# Sheet2.net
KiCad netlist of a schematic drawn in Altium Designer
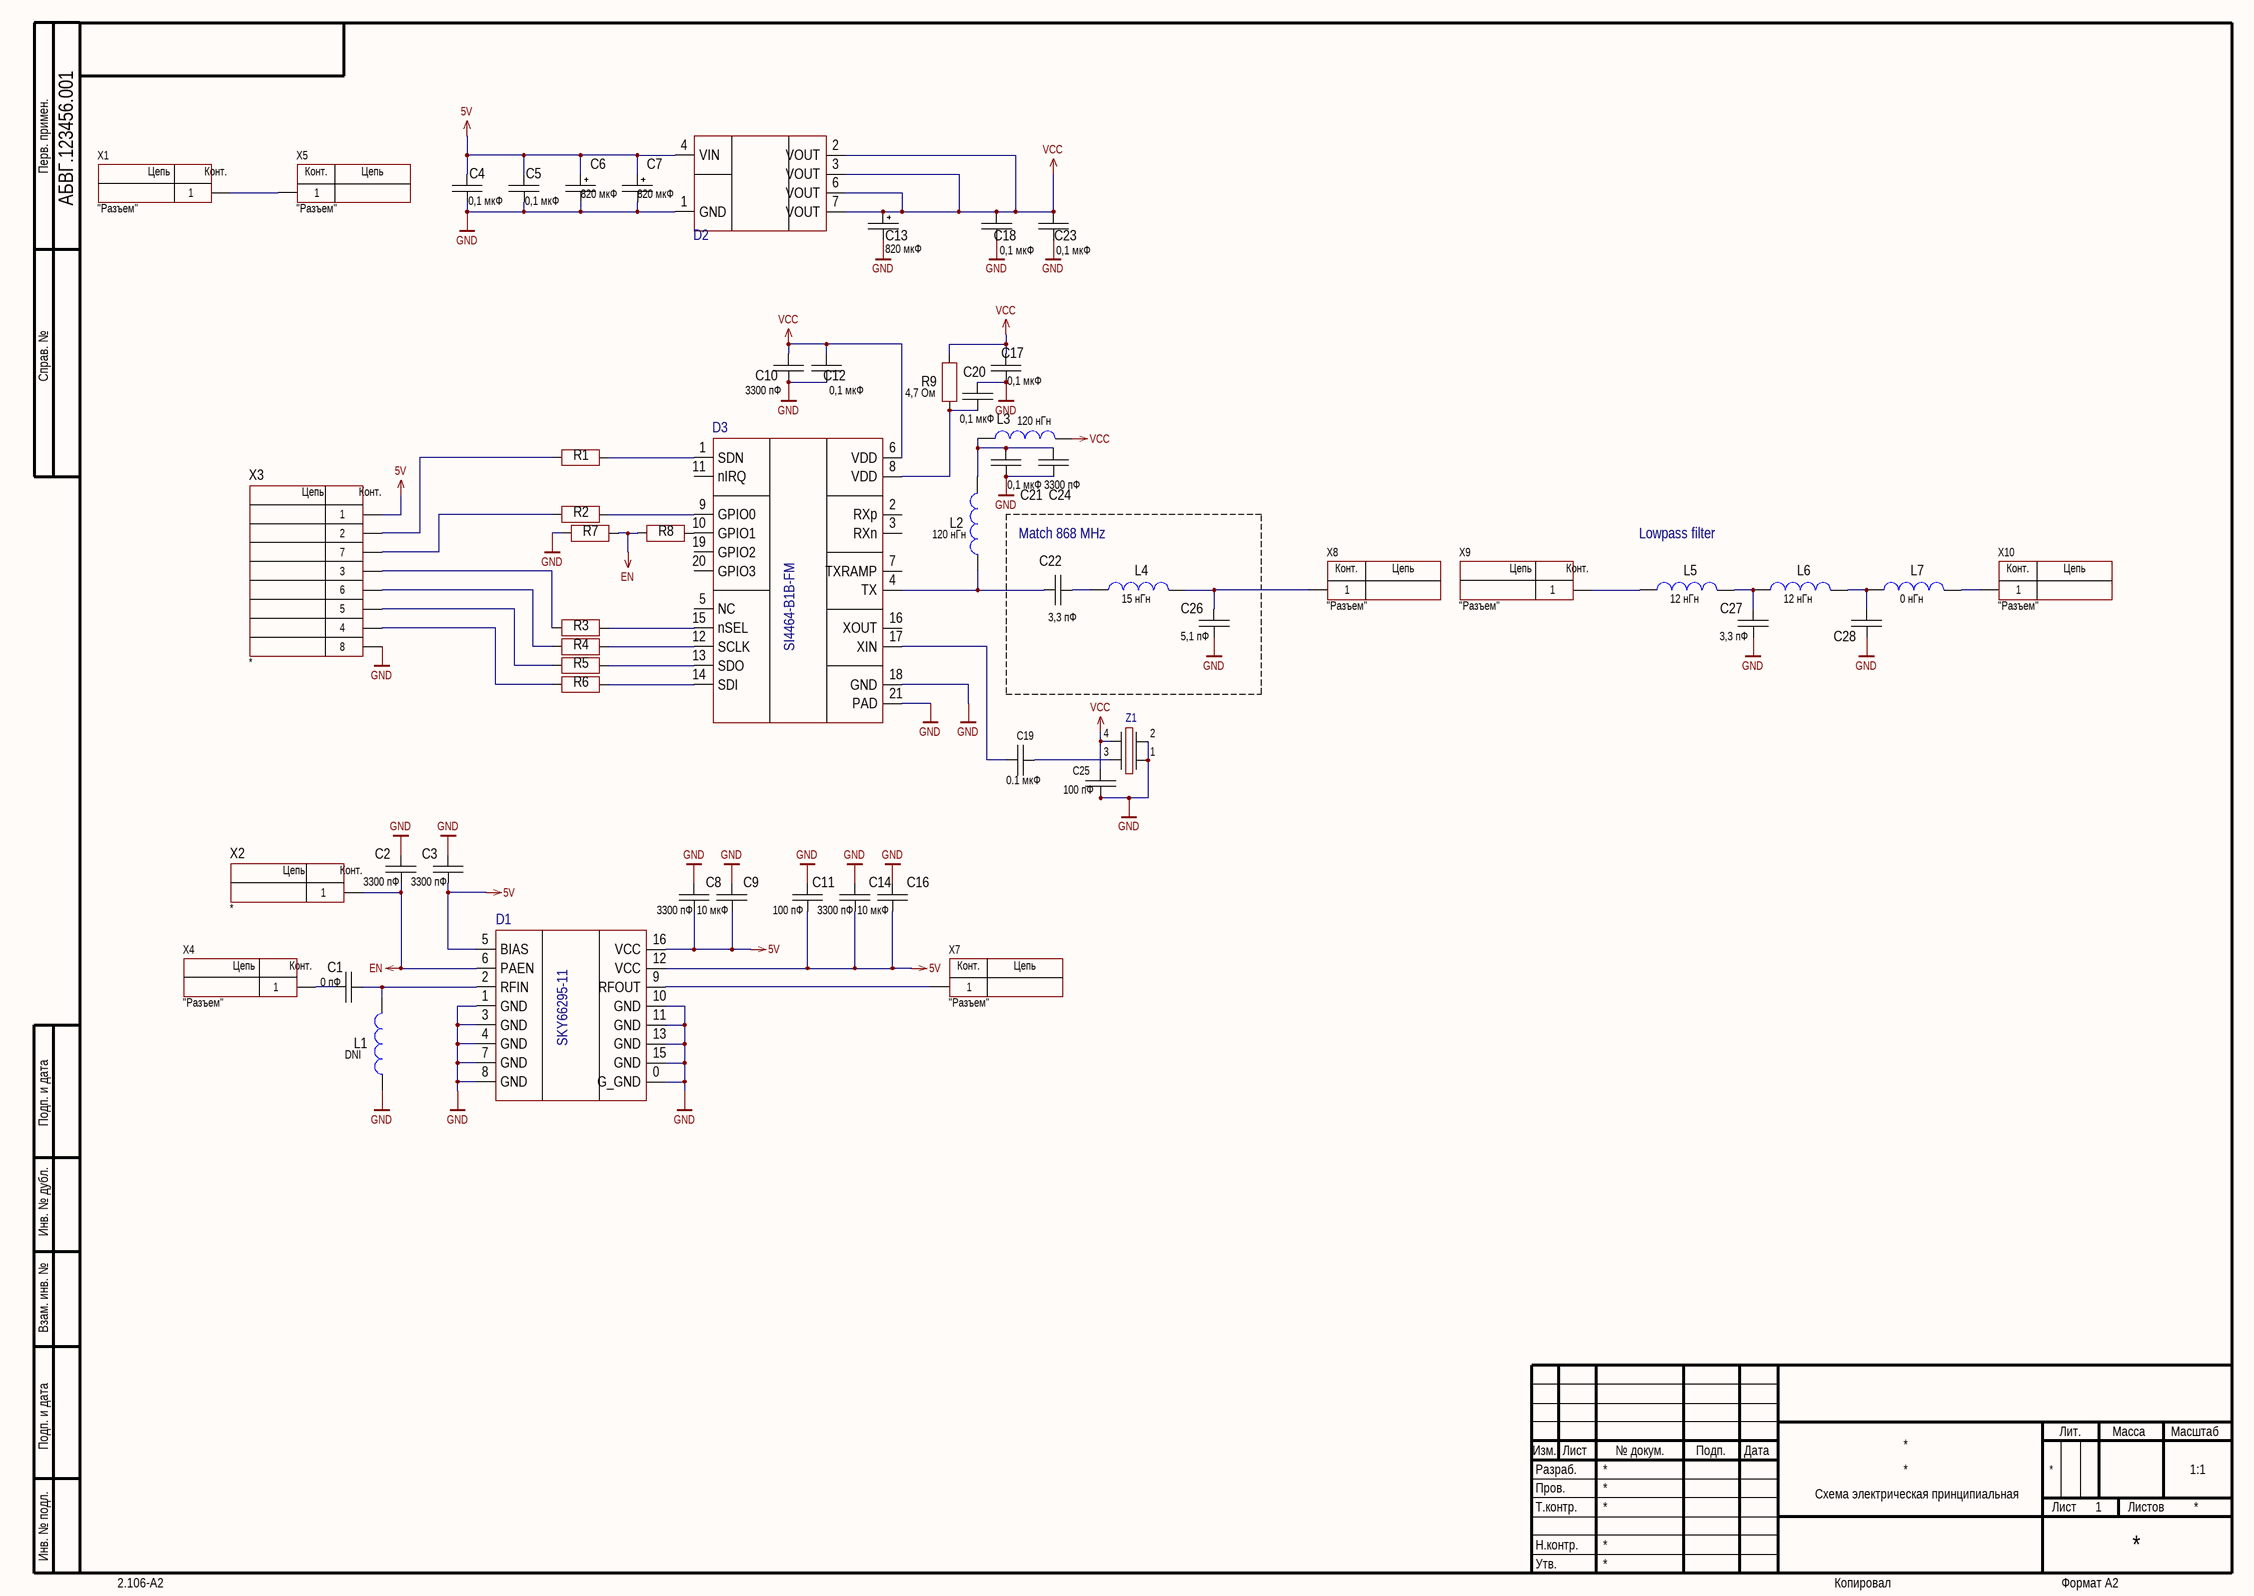
[diagram p0: Sheet2.SchDoc]

(export (version "E")
  (design (tool "Eeschema 10.0.6"))
  (components
    (comp (ref "C1")
      (value "0 пФ")
      (footprint "CH0603C")
      (fields
        (field (name "MANUFACTURER") "MURATA")
        (field (name "TOLERANCE") "±5%")
        (field (name "VALUEMANUFACTURERPARTNUMBER") "0603-NP0-50В-0 пФ±5% MURATA")
      )
      (libsource (lib "Discrete") (part "Capacitor"))
    )
    (comp (ref "C2")
      (value "3300 пФ")
      (footprint "CH0603C")
      (fields
        (field (name "MANUFACTURER") "MURATA")
        (field (name "TOLERANCE") "±5%")
        (field (name "VALUEMANUFACTURERPARTNUMBER") "0603-NP0-50В-3300 пФ±5% MURATA")
      )
      (libsource (lib "Discrete") (part "Capacitor"))
    )
    (comp (ref "C3")
      (value "3300 пФ")
      (footprint "CH0603C")
      (fields
        (field (name "MANUFACTURER") "MURATA")
        (field (name "TOLERANCE") "±5%")
        (field (name "VALUEMANUFACTURERPARTNUMBER") "0603-NP0-50В-3300 пФ±5% MURATA")
      )
      (libsource (lib "Discrete") (part "Capacitor"))
    )
    (comp (ref "C4")
      (value "0,1 мкФ")
      (footprint "CH0603C")
      (fields
        (field (name "MANUFACTURER") "MURATA")
        (field (name "TOLERANCE") "±5%")
        (field (name "VALUEMANUFACTURERPARTNUMBER") "0603-X7R-50В-0,1 мкФ±5% MURATA")
      )
      (libsource (lib "Discrete") (part "Capacitor"))
    )
    (comp (ref "C5")
      (value "0,1 мкФ")
      (footprint "CH0603C")
      (fields
        (field (name "MANUFACTURER") "MURATA")
        (field (name "TOLERANCE") "±5%")
        (field (name "VALUEMANUFACTURERPARTNUMBER") "0603-X7R-50В-0,1 мкФ±5% MURATA")
      )
      (libsource (lib "Discrete") (part "Capacitor"))
    )
    (comp (ref "C6")
      (value "820 мкФ")
      (footprint "D8C3.5H12")
      (fields (field (name "MANUFACTURER") "KEMET"))
      (libsource (lib "Discrete") (part "AlumCap"))
    )
    (comp (ref "C7")
      (value "820 мкФ")
      (footprint "D8C3.5H12")
      (fields (field (name "MANUFACTURER") "KEMET"))
      (libsource (lib "Discrete") (part "AlumCap"))
    )
    (comp (ref "C8")
      (value "3300 пФ")
      (footprint "CH0603C")
      (fields
        (field (name "MANUFACTURER") "MURATA")
        (field (name "TOLERANCE") "±5%")
        (field (name "VALUEMANUFACTURERPARTNUMBER") "0603-NP0-50В-3300 пФ±5% MURATA")
      )
      (libsource (lib "Discrete") (part "Capacitor"))
    )
    (comp (ref "C9")
      (value "10 мкФ")
      (footprint "CH1206C")
      (fields
        (field (name "MANUFACTURER") "MURATA")
        (field (name "TOLERANCE") "±5%")
        (field (name "VALUEMANUFACTURERPARTNUMBER") "1206-X7R-50В-10 мкФ±5% MURATA")
      )
      (libsource (lib "Discrete") (part "Capacitor"))
    )
    (comp (ref "C10")
      (value "3300 пФ")
      (footprint "CH0603C")
      (fields
        (field (name "MANUFACTURER") "MURATA")
        (field (name "TOLERANCE") "±5%")
        (field (name "VALUEMANUFACTURERPARTNUMBER") "0603-NP0-50В-3300 пФ±5% MURATA")
      )
      (libsource (lib "Discrete") (part "Capacitor"))
    )
    (comp (ref "C11")
      (value "100 пФ")
      (footprint "CH0603C")
      (fields
        (field (name "MANUFACTURER") "MURATA")
        (field (name "TOLERANCE") "±5%")
        (field (name "VALUEMANUFACTURERPARTNUMBER") "0603-NP0-50В-100 пФ±5% MURATA")
      )
      (libsource (lib "Discrete") (part "Capacitor"))
    )
    (comp (ref "C12")
      (value "0,1 мкФ")
      (footprint "CH0603C")
      (fields
        (field (name "MANUFACTURER") "MURATA")
        (field (name "TOLERANCE") "±5%")
        (field (name "VALUEMANUFACTURERPARTNUMBER") "0603-X7R-50В-0,1 мкФ±5% MURATA")
      )
      (libsource (lib "Discrete") (part "Capacitor"))
    )
    (comp (ref "C13")
      (value "820 мкФ")
      (footprint "D8C3.5H12")
      (fields (field (name "MANUFACTURER") "KEMET"))
      (libsource (lib "Discrete") (part "AlumCap"))
    )
    (comp (ref "C14")
      (value "3300 пФ")
      (footprint "CH0603C")
      (fields
        (field (name "MANUFACTURER") "MURATA")
        (field (name "TOLERANCE") "±5%")
        (field (name "VALUEMANUFACTURERPARTNUMBER") "0603-NP0-50В-3300 пФ±5% MURATA")
      )
      (libsource (lib "Discrete") (part "Capacitor"))
    )
    (comp (ref "C16")
      (value "10 мкФ")
      (footprint "CH1206C")
      (fields
        (field (name "MANUFACTURER") "MURATA")
        (field (name "TOLERANCE") "±5%")
        (field (name "VALUEMANUFACTURERPARTNUMBER") "1206-X7R-50В-10 мкФ±5% MURATA")
      )
      (libsource (lib "Discrete") (part "Capacitor"))
    )
    (comp (ref "C17")
      (value "0,1 мкФ")
      (footprint "CH0603C")
      (fields
        (field (name "MANUFACTURER") "MURATA")
        (field (name "TOLERANCE") "±5%")
        (field (name "VALUEMANUFACTURERPARTNUMBER") "0603-X7R-50В-0,1 мкФ±5% MURATA")
      )
      (libsource (lib "Discrete") (part "Capacitor"))
    )
    (comp (ref "C18")
      (value "0,1 мкФ")
      (footprint "CH0603C")
      (fields
        (field (name "MANUFACTURER") "MURATA")
        (field (name "TOLERANCE") "±5%")
        (field (name "VALUEMANUFACTURERPARTNUMBER") "0603-X7R-50В-0,1 мкФ±5% MURATA")
      )
      (libsource (lib "Discrete") (part "Capacitor"))
    )
    (comp (ref "C19")
      (value "0.1 мкФ")
      (footprint "CAP: 0603")
      (fields
        (field (name "MANUFACTURER") "Yageo")
        (field (name "PARTNUMBER") "CC0603KRX7R7BB104")
        (field (name "VALUEMANUFACTURERPARTNUMBER") "Ceramic capacitor, 0.1 мкФ, X7R, ±10%, 16V, 0603, -55...+125°C")
      )
      (libsource (lib "Capacitor") (part "Ceramic_0603"))
    )
    (comp (ref "C20")
      (value "0,1 мкФ")
      (footprint "CH0603C")
      (fields
        (field (name "MANUFACTURER") "MURATA")
        (field (name "TOLERANCE") "±5%")
        (field (name "VALUEMANUFACTURERPARTNUMBER") "0603-X7R-50В-0,1 мкФ±5% MURATA")
      )
      (libsource (lib "Discrete") (part "Capacitor"))
    )
    (comp (ref "C21")
      (value "0,1 мкФ")
      (footprint "CH0603C")
      (fields
        (field (name "MANUFACTURER") "MURATA")
        (field (name "TOLERANCE") "±5%")
        (field (name "VALUEMANUFACTURERPARTNUMBER") "0603-X7R-50В-0,1 мкФ±5% MURATA")
      )
      (libsource (lib "Discrete") (part "Capacitor"))
    )
    (comp (ref "C22")
      (value "3,3 пФ")
      (footprint "CH0603C")
      (fields
        (field (name "MANUFACTURER") "MURATA")
        (field (name "TOLERANCE") "±5%")
        (field (name "VALUEMANUFACTURERPARTNUMBER") "0603-NP0-50В-3,3 пФ±5% MURATA")
      )
      (libsource (lib "Discrete") (part "Capacitor"))
    )
    (comp (ref "C23")
      (value "0,1 мкФ")
      (footprint "CH0603C")
      (fields
        (field (name "MANUFACTURER") "MURATA")
        (field (name "TOLERANCE") "±5%")
        (field (name "VALUEMANUFACTURERPARTNUMBER") "0603-X7R-50В-0,1 мкФ±5% MURATA")
      )
      (libsource (lib "Discrete") (part "Capacitor"))
    )
    (comp (ref "C24")
      (value "3300 пФ")
      (footprint "CH0603C")
      (fields
        (field (name "MANUFACTURER") "MURATA")
        (field (name "TOLERANCE") "±5%")
        (field (name "VALUEMANUFACTURERPARTNUMBER") "0603-NP0-50В-3300 пФ±5% MURATA")
      )
      (libsource (lib "Discrete") (part "Capacitor"))
    )
    (comp (ref "C25")
      (value "100 пФ")
      (footprint "CAP: 0603")
      (fields
        (field (name "MANUFACTURER") "Yageo")
        (field (name "PARTNUMBER") "CC0603KRX7R7BB104")
        (field (name "VALUEMANUFACTURERPARTNUMBER") "Ceramic capacitor, 100 пФ, NP0, ±10%, 16V, 0603, -55...+125°C")
      )
      (libsource (lib "Capacitor") (part "Ceramic_0603"))
    )
    (comp (ref "C26")
      (value "5,1 пФ")
      (footprint "CH0603C")
      (fields
        (field (name "MANUFACTURER") "MURATA")
        (field (name "TOLERANCE") "±5%")
        (field (name "VALUEMANUFACTURERPARTNUMBER") "0603-NP0-50В-5,1 пФ±5% MURATA")
      )
      (libsource (lib "Discrete") (part "Capacitor"))
    )
    (comp (ref "C27")
      (value "3,3 пФ")
      (footprint "CH0603C")
      (fields
        (field (name "MANUFACTURER") "MURATA")
        (field (name "TOLERANCE") "±5%")
        (field (name "VALUEMANUFACTURERPARTNUMBER") "0603-NP0-50В-3,3 пФ±5% MURATA")
      )
      (libsource (lib "Discrete") (part "Capacitor"))
    )
    (comp (ref "C28")
      (value "10 пФ")
      (footprint "CH0603C")
      (fields
        (field (name "MANUFACTURER") "MURATA")
        (field (name "TOLERANCE") "±5%")
        (field (name "VALUEMANUFACTURERPARTNUMBER") "0603-NP0-50В-10 пФ±5% MURATA")
      )
      (libsource (lib "Discrete") (part "Capacitor"))
    )
    (comp (ref "D1")
      (value "SKY66295-11")
      (footprint "16-LGA (5x5)")
      (description "800 to 900 MHz High-Efficiency 4 W Power Amplifier")
      (fields (field (name "VALUEMANUFACTURERPARTNUMBER") "SKY66295-11 *"))
      (libsource (lib "Analog") (part "SKY66295-11"))
    )
    (comp (ref "D2")
      (value "LD1117D33")
      (footprint "8-SOIC")
      (fields (field (name "MANUFACTURER") "ST MICROELECTRONICS"))
      (libsource (lib "Power Supplies") (part "LD1117D33"))
    )
    (comp (ref "D3")
      (value "SI4464-B1B-FM")
      (footprint "20-QFN (4x4)")
      (description "RF Transceiver FSK/GFSK/GMSK/MSK/OOK 3.3V 20-Pin QFN")
      (fields
        (field (name "MANUFACTURER") "SILICON LABS")
        (field (name "VALUEMANUFACTURERPARTNUMBER") "SI4464-B1B-FM SILICON LABS")
      )
      (libsource (lib "Digital") (part "SI4464"))
    )
    (comp (ref "L1")
      (value "DNI")
      (footprint "CH0603L")
      (fields (field (name "TOLERANCE") "±5%") (field (name "VALUEMANUFACTURERPARTNUMBER") "* DNI ±5% *"))
      (libsource (lib "Discrete") (part "Inductor"))
    )
    (comp (ref "L2")
      (value "120 нГн")
      (footprint "CH0603L")
      (fields (field (name "TOLERANCE") "±5%") (field (name "VALUEMANUFACTURERPARTNUMBER") "* 120 нГн ±5% *"))
      (libsource (lib "Discrete") (part "Inductor"))
    )
    (comp (ref "L3")
      (value "120 нГн")
      (footprint "CH0603L")
      (fields (field (name "TOLERANCE") "±5%") (field (name "VALUEMANUFACTURERPARTNUMBER") "* 120 нГн ±5% *"))
      (libsource (lib "Discrete") (part "Inductor"))
    )
    (comp (ref "L4")
      (value "15 нГн")
      (footprint "CH0603L")
      (fields (field (name "TOLERANCE") "±5%") (field (name "VALUEMANUFACTURERPARTNUMBER") "* 15 нГн ±5% *"))
      (libsource (lib "Discrete") (part "Inductor"))
    )
    (comp (ref "L5")
      (value "12 нГн")
      (footprint "CH0603L")
      (fields (field (name "TOLERANCE") "±5%") (field (name "VALUEMANUFACTURERPARTNUMBER") "* 12 нГн ±5% *"))
      (libsource (lib "Discrete") (part "Inductor"))
    )
    (comp (ref "L6")
      (value "12 нГн")
      (footprint "CH0603L")
      (fields (field (name "TOLERANCE") "±5%") (field (name "VALUEMANUFACTURERPARTNUMBER") "* 12 нГн ±5% *"))
      (libsource (lib "Discrete") (part "Inductor"))
    )
    (comp (ref "L7")
      (value "0 нГн")
      (footprint "CH0603L")
      (fields (field (name "TOLERANCE") "±5%") (field (name "VALUEMANUFACTURERPARTNUMBER") "* 0 нГн ±5% *"))
      (libsource (lib "Discrete") (part "Inductor"))
    )
    (comp (ref "R1")
      (value "100 Ом")
      (footprint "CH0603R")
      (fields
        (field (name "MANUFACTURER") "YAGEO")
        (field (name "TOLERANCE") "± 5%")
        (field (name "VALUEMANUFACTURERPARTNUMBER") "RC0603-0,1-100 Ом ± 5% YAGEO")
      )
      (libsource (lib "Discrete") (part "Resistor"))
    )
    (comp (ref "R2")
      (value "100 Ом")
      (footprint "CH0603R")
      (fields
        (field (name "MANUFACTURER") "YAGEO")
        (field (name "TOLERANCE") "± 5%")
        (field (name "VALUEMANUFACTURERPARTNUMBER") "RC0603-0,1-100 Ом ± 5% YAGEO")
      )
      (libsource (lib "Discrete") (part "Resistor"))
    )
    (comp (ref "R3")
      (value "100 Ом")
      (footprint "CH0603R")
      (fields
        (field (name "MANUFACTURER") "YAGEO")
        (field (name "TOLERANCE") "± 5%")
        (field (name "VALUEMANUFACTURERPARTNUMBER") "RC0603-0,1-100 Ом ± 5% YAGEO")
      )
      (libsource (lib "Discrete") (part "Resistor"))
    )
    (comp (ref "R4")
      (value "100 Ом")
      (footprint "CH0603R")
      (fields
        (field (name "MANUFACTURER") "YAGEO")
        (field (name "TOLERANCE") "± 5%")
        (field (name "VALUEMANUFACTURERPARTNUMBER") "RC0603-0,1-100 Ом ± 5% YAGEO")
      )
      (libsource (lib "Discrete") (part "Resistor"))
    )
    (comp (ref "R5")
      (value "100 Ом")
      (footprint "CH0603R")
      (fields
        (field (name "MANUFACTURER") "YAGEO")
        (field (name "TOLERANCE") "± 5%")
        (field (name "VALUEMANUFACTURERPARTNUMBER") "RC0603-0,1-100 Ом ± 5% YAGEO")
      )
      (libsource (lib "Discrete") (part "Resistor"))
    )
    (comp (ref "R6")
      (value "100 Ом")
      (footprint "CH0603R")
      (fields
        (field (name "MANUFACTURER") "YAGEO")
        (field (name "TOLERANCE") "± 5%")
        (field (name "VALUEMANUFACTURERPARTNUMBER") "RC0603-0,1-100 Ом ± 5% YAGEO")
      )
      (libsource (lib "Discrete") (part "Resistor"))
    )
    (comp (ref "R7")
      (value "1 кОм")
      (footprint "CH0603R")
      (fields
        (field (name "MANUFACTURER") "YAGEO")
        (field (name "TOLERANCE") "± 5%")
        (field (name "VALUEMANUFACTURERPARTNUMBER") "RC0603-0,1-1 кОм ± 5% YAGEO")
      )
      (libsource (lib "Discrete") (part "Resistor"))
    )
    (comp (ref "R8")
      (value "1 кОм")
      (footprint "CH0603R")
      (fields
        (field (name "MANUFACTURER") "YAGEO")
        (field (name "TOLERANCE") "± 5%")
        (field (name "VALUEMANUFACTURERPARTNUMBER") "RC0603-0,1-1 кОм ± 5% YAGEO")
      )
      (libsource (lib "Discrete") (part "Resistor"))
    )
    (comp (ref "R9")
      (value "4,7 Ом")
      (footprint "CH0603R")
      (fields
        (field (name "MANUFACTURER") "YAGEO")
        (field (name "TOLERANCE") "± 5%")
        (field (name "VALUEMANUFACTURERPARTNUMBER") "RC0603-0,1-4,7 Ом ± 5% YAGEO")
      )
      (libsource (lib "") (part "Resistor_1"))
    )
    (comp (ref "X1")
      (value "~")
      (footprint "CON: SMA")
      (fields
        (field (name "MANUFACTURER") "TE Connectivity")
        (field (name "VALUEMANUFACTURERPARTNUMBER") "Connector SMA, 50 Ohm, 3GHz")
        (field (name "PARTNUMBER") "5-1814832-1")
        (field (name "COMMENTTEXT") "\"Разъем\"")
      )
      (libsource (lib "Connector") (part "Connector_SMA"))
    )
    (comp (ref "X2")
      (value "*")
      (footprint "CON: PADS 1x1mm")
      (libsource (lib "Connectors") (part "1-Connector"))
    )
    (comp (ref "X3") (value "*") (footprint "CON: PLS-8") (libsource (lib "Connectors") (part "8-Connector")))
    (comp (ref "X4")
      (value "~")
      (footprint "CON: SMA")
      (fields
        (field (name "MANUFACTURER") "TE Connectivity")
        (field (name "VALUEMANUFACTURERPARTNUMBER") "Connector SMA, 50 Ohm, 3GHz")
        (field (name "PARTNUMBER") "5-1814832-1")
        (field (name "COMMENTTEXT") "\"Разъем\"")
      )
      (libsource (lib "Connector") (part "Connector_SMA"))
    )
    (comp (ref "X5")
      (value "~")
      (footprint "CON: SMA")
      (fields
        (field (name "MANUFACTURER") "TE Connectivity")
        (field (name "VALUEMANUFACTURERPARTNUMBER") "Connector SMA, 50 Ohm, 3GHz")
        (field (name "PARTNUMBER") "5-1814832-1")
        (field (name "COMMENTTEXT") "\"Разъем\"")
      )
      (libsource (lib "") (part "Connector_SMA_1"))
    )
    (comp (ref "X7")
      (value "~")
      (footprint "CON: SMA")
      (fields
        (field (name "MANUFACTURER") "TE Connectivity")
        (field (name "VALUEMANUFACTURERPARTNUMBER") "Connector SMA, 50 Ohm, 3GHz")
        (field (name "PARTNUMBER") "5-1814832-1")
        (field (name "COMMENTTEXT") "\"Разъем\"")
      )
      (libsource (lib "") (part "Connector_SMA_1"))
    )
    (comp (ref "X8")
      (value "~")
      (footprint "CON: SMA")
      (fields
        (field (name "MANUFACTURER") "TE Connectivity")
        (field (name "VALUEMANUFACTURERPARTNUMBER") "Connector SMA, 50 Ohm, 3GHz")
        (field (name "PARTNUMBER") "5-1814832-1")
        (field (name "COMMENTTEXT") "\"Разъем\"")
      )
      (libsource (lib "") (part "Connector_SMA_1"))
    )
    (comp (ref "X9")
      (value "~")
      (footprint "CON: SMA")
      (fields
        (field (name "MANUFACTURER") "TE Connectivity")
        (field (name "VALUEMANUFACTURERPARTNUMBER") "Connector SMA, 50 Ohm, 3GHz")
        (field (name "PARTNUMBER") "5-1814832-1")
        (field (name "COMMENTTEXT") "\"Разъем\"")
      )
      (libsource (lib "Connector") (part "Connector_SMA"))
    )
    (comp (ref "X10")
      (value "~")
      (footprint "CON: SMA")
      (fields
        (field (name "MANUFACTURER") "TE Connectivity")
        (field (name "VALUEMANUFACTURERPARTNUMBER") "Connector SMA, 50 Ohm, 3GHz")
        (field (name "PARTNUMBER") "5-1814832-1")
        (field (name "COMMENTTEXT") "\"Разъем\"")
      )
      (libsource (lib "") (part "Connector_SMA_1"))
    )
    (comp (ref "Z1")
      (value "JT33-B-K-3,3-LF-26,0MHz")
      (footprint "OSC: 3225")
      (fields (field (name "MANUFACTURER") "JAUCH"))
      (libsource (lib "Oscilator") (part "Oscilator_3225"))
    )
  )
  (nets
    (net (code "1") (name "5V") (class "Default")
      (node (ref "C11") (pin "1") (pinfunction "1_1") (pintype "power_in"))
      (node (ref "C14") (pin "1") (pinfunction "1_1") (pintype "power_in"))
      (node (ref "C16") (pin "1") (pinfunction "1_1") (pintype "power_in"))
      (node (ref "C3") (pin "1") (pinfunction "1_1") (pintype "power_in"))
      (node (ref "C4") (pin "2") (pinfunction "2_2") (pintype "power_in"))
      (node (ref "C5") (pin "2") (pinfunction "2_2") (pintype "power_in"))
      (node (ref "C6") (pin "1") (pinfunction "1_1") (pintype "power_in"))
      (node (ref "C7") (pin "1") (pinfunction "1_1") (pintype "power_in"))
      (node (ref "C8") (pin "1") (pinfunction "1_1") (pintype "power_in"))
      (node (ref "C9") (pin "1") (pinfunction "1_1") (pintype "power_in"))
      (node (ref "D1") (pin "12") (pinfunction "VCC_12") (pintype "passive"))
      (node (ref "D1") (pin "16") (pinfunction "VCC_16") (pintype "passive"))
      (node (ref "D1") (pin "5") (pinfunction "BIAS_5") (pintype "passive"))
      (node (ref "D2") (pin "4") (pinfunction "VIN_4") (pintype "power_in"))
      (node (ref "X3") (pin "1") (pinfunction "1_1") (pintype "passive"))
    )
    (net (code "2") (name "EN") (class "Default")
      (node (ref "C2") (pin "1") (pinfunction "1_1") (pintype "power_in"))
      (node (ref "D1") (pin "6") (pinfunction "PAEN_6") (pintype "passive"))
      (node (ref "R7") (pin "1") (pinfunction "1_1") (pintype "passive"))
      (node (ref "R8") (pin "2") (pinfunction "2_2") (pintype "passive"))
      (node (ref "X2") (pin "1") (pinfunction "1_1") (pintype "passive"))
    )
    (net (code "3") (name "GND") (class "Default")
      (node (ref "C10") (pin "1") (pinfunction "1_1") (pintype "power_in"))
      (node (ref "C11") (pin "2") (pinfunction "2_2") (pintype "power_in"))
      (node (ref "C12") (pin "1") (pinfunction "1_1") (pintype "power_in"))
      (node (ref "C13") (pin "2") (pinfunction "2_2") (pintype "power_in"))
      (node (ref "C14") (pin "2") (pinfunction "2_2") (pintype "power_in"))
      (node (ref "C16") (pin "2") (pinfunction "2_2") (pintype "power_in"))
      (node (ref "C17") (pin "1") (pinfunction "1_1") (pintype "power_in"))
      (node (ref "C18") (pin "1") (pinfunction "1_1") (pintype "power_in"))
      (node (ref "C2") (pin "2") (pinfunction "2_2") (pintype "power_in"))
      (node (ref "C20") (pin "2") (pinfunction "2_2") (pintype "power_in"))
      (node (ref "C21") (pin "1") (pinfunction "1_1") (pintype "power_in"))
      (node (ref "C23") (pin "1") (pinfunction "1_1") (pintype "power_in"))
      (node (ref "C24") (pin "1") (pinfunction "1_1") (pintype "power_in"))
      (node (ref "C25") (pin "1") (pinfunction "1_1") (pintype "power_in"))
      (node (ref "C26") (pin "1") (pinfunction "1_1") (pintype "power_in"))
      (node (ref "C27") (pin "1") (pinfunction "1_1") (pintype "power_in"))
      (node (ref "C28") (pin "1") (pinfunction "1_1") (pintype "power_in"))
      (node (ref "C3") (pin "2") (pinfunction "2_2") (pintype "power_in"))
      (node (ref "C4") (pin "1") (pinfunction "1_1") (pintype "power_in"))
      (node (ref "C5") (pin "1") (pinfunction "1_1") (pintype "power_in"))
      (node (ref "C6") (pin "2") (pinfunction "2_2") (pintype "power_in"))
      (node (ref "C7") (pin "2") (pinfunction "2_2") (pintype "power_in"))
      (node (ref "C8") (pin "2") (pinfunction "2_2") (pintype "power_in"))
      (node (ref "C9") (pin "2") (pinfunction "2_2") (pintype "power_in"))
      (node (ref "D1") (pin "0") (pinfunction "G_GND_0") (pintype "passive"))
      (node (ref "D1") (pin "1") (pinfunction "GND_1") (pintype "passive"))
      (node (ref "D1") (pin "10") (pinfunction "GND_10") (pintype "passive"))
      (node (ref "D1") (pin "11") (pinfunction "GND_11") (pintype "passive"))
      (node (ref "D1") (pin "13") (pinfunction "GND_13") (pintype "passive"))
      (node (ref "D1") (pin "15") (pinfunction "GND_15") (pintype "passive"))
      (node (ref "D1") (pin "3") (pinfunction "GND_3") (pintype "passive"))
      (node (ref "D1") (pin "4") (pinfunction "GND_4") (pintype "passive"))
      (node (ref "D1") (pin "7") (pinfunction "GND_7") (pintype "passive"))
      (node (ref "D1") (pin "8") (pinfunction "GND_8") (pintype "passive"))
      (node (ref "D2") (pin "1") (pinfunction "GND_1") (pintype "power_in"))
      (node (ref "D3") (pin "18") (pinfunction "GND_18") (pintype "passive"))
      (node (ref "D3") (pin "21") (pinfunction "PAD_21") (pintype "passive"))
      (node (ref "L1") (pin "2") (pinfunction "2_2") (pintype "passive"))
      (node (ref "R7") (pin "2") (pinfunction "2_2") (pintype "passive"))
      (node (ref "X3") (pin "8") (pinfunction "8_8") (pintype "power_in"))
      (node (ref "Z1") (pin "1") (pinfunction "1_1") (pintype "passive"))
      (node (ref "Z1") (pin "2") (pinfunction "2_2") (pintype "passive"))
    )
    (net (code "4") (name "Net-(C1-Pad2)") (class "Default")
      (node (ref "C1") (pin "2") (pinfunction "2_2") (pintype "power_in"))
      (node (ref "X4") (pin "1") (pinfunction "1_1") (pintype "passive"))
    )
    (net (code "5") (name "Net-(C19-Pad1)") (class "Default")
      (node (ref "C19") (pin "1") (pinfunction "1_1") (pintype "power_in"))
      (node (ref "Z1") (pin "3") (pinfunction "3_3") (pintype "passive"))
    )
    (net (code "6") (name "Net-(C20-Pad1)") (class "Default")
      (node (ref "C20") (pin "1") (pinfunction "1_1") (pintype "power_in"))
      (node (ref "D3") (pin "8") (pinfunction "VDD_8") (pintype "passive"))
      (node (ref "R9") (pin "2") (pinfunction "2_2") (pintype "passive"))
    )
    (net (code "7") (name "Net-(C21-Pad2)") (class "Default")
      (node (ref "C21") (pin "2") (pinfunction "2_2") (pintype "power_in"))
      (node (ref "C24") (pin "2") (pinfunction "2_2") (pintype "power_in"))
      (node (ref "L2") (pin "1") (pinfunction "1_1") (pintype "passive"))
      (node (ref "L3") (pin "2") (pinfunction "2_2") (pintype "passive"))
    )
    (net (code "8") (name "Net-(C22-Pad1)") (class "Default")
      (node (ref "C22") (pin "1") (pinfunction "1_1") (pintype "power_in"))
      (node (ref "L4") (pin "2") (pinfunction "2_2") (pintype "passive"))
    )
    (net (code "9") (name "Net-(C26-Pad2)") (class "Default")
      (node (ref "C26") (pin "2") (pinfunction "2_2") (pintype "power_in"))
      (node (ref "L4") (pin "1") (pinfunction "1_1") (pintype "passive"))
      (node (ref "X8") (pin "1") (pinfunction "1_1") (pintype "passive"))
    )
    (net (code "10") (name "Net-(C27-Pad2)") (class "Default")
      (node (ref "C27") (pin "2") (pinfunction "2_2") (pintype "power_in"))
      (node (ref "L5") (pin "1") (pinfunction "1_1") (pintype "passive"))
      (node (ref "L6") (pin "2") (pinfunction "2_2") (pintype "passive"))
    )
    (net (code "11") (name "Net-(C28-Pad2)") (class "Default")
      (node (ref "C28") (pin "2") (pinfunction "2_2") (pintype "power_in"))
      (node (ref "L6") (pin "1") (pinfunction "1_1") (pintype "passive"))
      (node (ref "L7") (pin "2") (pinfunction "2_2") (pintype "passive"))
    )
    (net (code "12") (name "Net-(D1-RFIN)") (class "Default")
      (node (ref "C1") (pin "1") (pinfunction "1_1") (pintype "power_in"))
      (node (ref "D1") (pin "2") (pinfunction "RFIN_2") (pintype "passive"))
      (node (ref "L1") (pin "1") (pinfunction "1_1") (pintype "passive"))
    )
    (net (code "13") (name "Net-(D1-RFOUT)") (class "Default")
      (node (ref "D1") (pin "9") (pinfunction "RFOUT_9") (pintype "passive"))
      (node (ref "X7") (pin "1") (pinfunction "1_1") (pintype "passive"))
    )
    (net (code "14") (name "Net-(D3-GPIO0)") (class "Default")
      (node (ref "D3") (pin "9") (pinfunction "GPIO0_9") (pintype "passive"))
      (node (ref "R2") (pin "1") (pinfunction "1_1") (pintype "passive"))
    )
    (net (code "15") (name "Net-(D3-GPIO1)") (class "Default")
      (node (ref "D3") (pin "10") (pinfunction "GPIO1_10") (pintype "passive"))
      (node (ref "R8") (pin "1") (pinfunction "1_1") (pintype "passive"))
    )
    (net (code "16") (name "Net-(D3-SCLK)") (class "Default")
      (node (ref "D3") (pin "12") (pinfunction "SCLK_12") (pintype "passive"))
      (node (ref "R4") (pin "1") (pinfunction "1_1") (pintype "passive"))
    )
    (net (code "17") (name "Net-(D3-SDI)") (class "Default")
      (node (ref "D3") (pin "14") (pinfunction "SDI_14") (pintype "passive"))
      (node (ref "R6") (pin "1") (pinfunction "1_1") (pintype "passive"))
    )
    (net (code "18") (name "Net-(D3-SDN)") (class "Default")
      (node (ref "D3") (pin "1") (pinfunction "SDN_1") (pintype "passive"))
      (node (ref "R1") (pin "1") (pinfunction "1_1") (pintype "passive"))
    )
    (net (code "19") (name "Net-(D3-SDO)") (class "Default")
      (node (ref "D3") (pin "13") (pinfunction "SDO_13") (pintype "passive"))
      (node (ref "R5") (pin "1") (pinfunction "1_1") (pintype "passive"))
    )
    (net (code "20") (name "Net-(D3-TX)") (class "Default")
      (node (ref "C22") (pin "2") (pinfunction "2_2") (pintype "power_in"))
      (node (ref "D3") (pin "4") (pinfunction "TX_4") (pintype "passive"))
      (node (ref "L2") (pin "2") (pinfunction "2_2") (pintype "passive"))
    )
    (net (code "21") (name "Net-(D3-XIN)") (class "Default")
      (node (ref "C19") (pin "2") (pinfunction "2_2") (pintype "power_in"))
      (node (ref "D3") (pin "17") (pinfunction "XIN_17") (pintype "passive"))
    )
    (net (code "22") (name "Net-(D3-nSEL)") (class "Default")
      (node (ref "D3") (pin "15") (pinfunction "nSEL_15") (pintype "passive"))
      (node (ref "R3") (pin "1") (pinfunction "1_1") (pintype "passive"))
    )
    (net (code "23") (name "Net-(L5-Pad2)") (class "Default")
      (node (ref "L5") (pin "2") (pinfunction "2_2") (pintype "passive"))
      (node (ref "X9") (pin "1") (pinfunction "1_1") (pintype "passive"))
    )
    (net (code "24") (name "Net-(L7-Pad1)") (class "Default")
      (node (ref "L7") (pin "1") (pinfunction "1_1") (pintype "passive"))
      (node (ref "X10") (pin "1") (pinfunction "1_1") (pintype "passive"))
    )
    (net (code "25") (name "Net-(R1-Pad2)") (class "Default")
      (node (ref "R1") (pin "2") (pinfunction "2_2") (pintype "passive"))
      (node (ref "X3") (pin "2") (pinfunction "2_2") (pintype "passive"))
    )
    (net (code "26") (name "Net-(R2-Pad2)") (class "Default")
      (node (ref "R2") (pin "2") (pinfunction "2_2") (pintype "passive"))
      (node (ref "X3") (pin "7") (pinfunction "7_7") (pintype "power_in"))
    )
    (net (code "27") (name "Net-(R3-Pad2)") (class "Default")
      (node (ref "R3") (pin "2") (pinfunction "2_2") (pintype "passive"))
      (node (ref "X3") (pin "3") (pinfunction "3_3") (pintype "power_in"))
    )
    (net (code "28") (name "Net-(R4-Pad2)") (class "Default")
      (node (ref "R4") (pin "2") (pinfunction "2_2") (pintype "passive"))
      (node (ref "X3") (pin "6") (pinfunction "6_6") (pintype "power_in"))
    )
    (net (code "29") (name "Net-(R5-Pad2)") (class "Default")
      (node (ref "R5") (pin "2") (pinfunction "2_2") (pintype "passive"))
      (node (ref "X3") (pin "5") (pinfunction "5_5") (pintype "power_in"))
    )
    (net (code "30") (name "Net-(R6-Pad2)") (class "Default")
      (node (ref "R6") (pin "2") (pinfunction "2_2") (pintype "passive"))
      (node (ref "X3") (pin "4") (pinfunction "4_4") (pintype "power_in"))
    )
    (net (code "31") (name "Net-(X1-Pad1)") (class "Default")
      (node (ref "X1") (pin "1") (pinfunction "1_1") (pintype "passive"))
      (node (ref "X5") (pin "1") (pinfunction "1_1") (pintype "passive"))
    )
    (net (code "32") (name "VCC") (class "Default")
      (node (ref "C10") (pin "2") (pinfunction "2_2") (pintype "power_in"))
      (node (ref "C12") (pin "2") (pinfunction "2_2") (pintype "power_in"))
      (node (ref "C13") (pin "1") (pinfunction "1_1") (pintype "power_in"))
      (node (ref "C17") (pin "2") (pinfunction "2_2") (pintype "power_in"))
      (node (ref "C18") (pin "2") (pinfunction "2_2") (pintype "power_in"))
      (node (ref "C23") (pin "2") (pinfunction "2_2") (pintype "power_in"))
      (node (ref "C25") (pin "2") (pinfunction "2_2") (pintype "power_in"))
      (node (ref "D2") (pin "2") (pinfunction "VOUT_2") (pintype "power_in"))
      (node (ref "D2") (pin "3") (pinfunction "VOUT_3") (pintype "power_in"))
      (node (ref "D2") (pin "6") (pinfunction "VOUT_6") (pintype "passive"))
      (node (ref "D2") (pin "7") (pinfunction "VOUT_7") (pintype "passive"))
      (node (ref "D3") (pin "6") (pinfunction "VDD_6") (pintype "passive"))
      (node (ref "L3") (pin "1") (pinfunction "1_1") (pintype "passive"))
      (node (ref "R9") (pin "1") (pinfunction "1_1") (pintype "passive"))
      (node (ref "Z1") (pin "4") (pinfunction "4_4") (pintype "passive"))
    )
    (net (code "33") (name "unconnected-(D3-GPIO2-Pad19)") (class "Default")
      (node (ref "D3") (pin "19") (pinfunction "GPIO2_19") (pintype "passive"))
    )
    (net (code "34") (name "unconnected-(D3-GPIO3-Pad20)") (class "Default")
      (node (ref "D3") (pin "20") (pinfunction "GPIO3_20") (pintype "passive"))
    )
    (net (code "35") (name "unconnected-(D3-NC-Pad5)") (class "Default")
      (node (ref "D3") (pin "5") (pinfunction "NC_5") (pintype "passive"))
    )
    (net (code "36") (name "unconnected-(D3-RXn-Pad3)") (class "Default")
      (node (ref "D3") (pin "3") (pinfunction "RXn_3") (pintype "passive"))
    )
    (net (code "37") (name "unconnected-(D3-RXp-Pad2)") (class "Default")
      (node (ref "D3") (pin "2") (pinfunction "RXp_2") (pintype "passive"))
    )
    (net (code "38") (name "unconnected-(D3-TXRAMP-Pad7)") (class "Default")
      (node (ref "D3") (pin "7") (pinfunction "TXRAMP_7") (pintype "passive"))
    )
    (net (code "39") (name "unconnected-(D3-XOUT-Pad16)") (class "Default")
      (node (ref "D3") (pin "16") (pinfunction "XOUT_16") (pintype "passive"))
    )
    (net (code "40") (name "unconnected-(D3-nIRQ-Pad11)") (class "Default")
      (node (ref "D3") (pin "11") (pinfunction "nIRQ_11") (pintype "passive"))
    )
  )
)
